# PotsDuino.net
KiCad netlist of a schematic drawn in Altium Designer
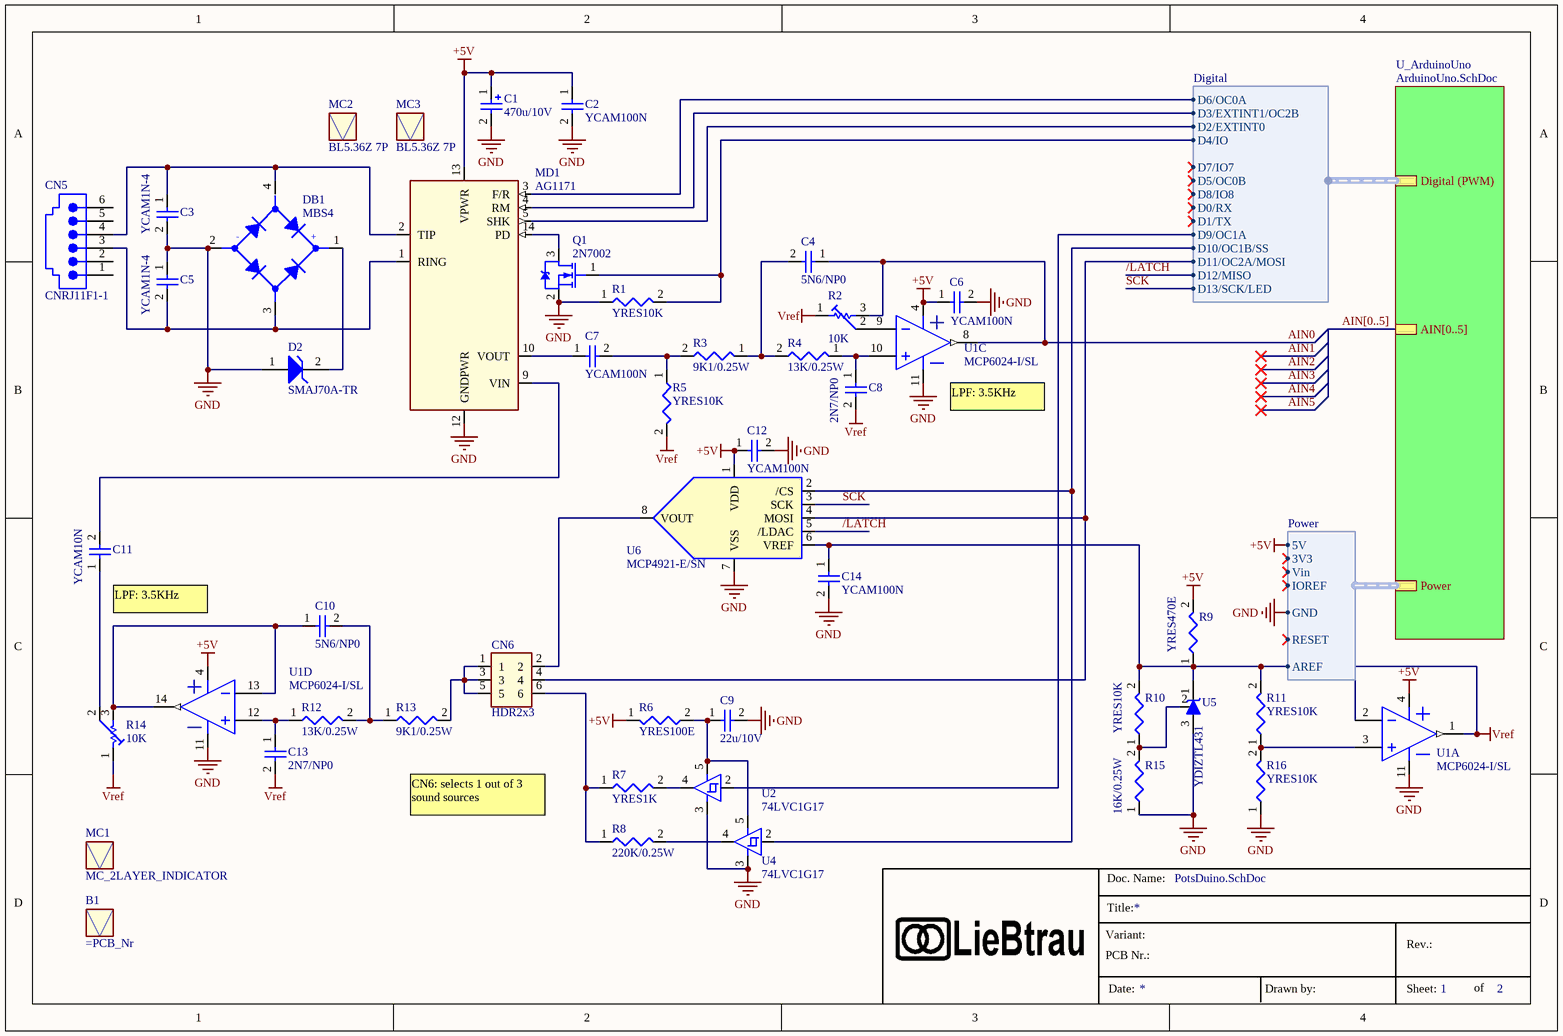
[diagram p0: PotsDuino.SchDoc]

(export (version "E")
  (design (tool "Eeschema 10.0.6"))
  (components
    (comp (ref "B1")
      (value "~")
      (fields (field (name "PART NUMBER") "BARE_PCB"))
      (libsource (lib "Testing") (part "BD_PCB"))
    )
    (comp (ref "C1")
      (value "470u/10V")
      (footprint "CA_CANSMD103_H100")
      (fields (field (name "PART NUMBER") "EEEFC1A471P") (field (name "MANUFACTURER") "Panasonic"))
      (libsource (lib "Testing") (part "CA_POL"))
    )
    (comp (ref "C2") (value "YCAM100N") (footprint "CA_1206") (libsource (lib "Testing") (part "CA_NONPOL")))
    (comp (ref "C3")
      (value "YCAM1N-4")
      (footprint "CA_1206_H16")
      (fields (field (name "MANUFACTURER") "AVX"))
      (libsource (lib "Testing") (part "CA_NONPOL"))
    )
    (comp (ref "C4")
      (value "5N6/NP0")
      (footprint "CA_0603")
      (fields (field (name "PART NUMBER") "C0603C562J5GACTU") (field (name "MANUFACTURER") "KEMET"))
      (libsource (lib "Testing") (part "CA_NONPOL"))
    )
    (comp (ref "C5")
      (value "YCAM1N-4")
      (footprint "CA_1206_H16")
      (fields (field (name "MANUFACTURER") "AVX"))
      (libsource (lib "Testing") (part "CA_NONPOL"))
    )
    (comp (ref "C6") (value "YCAM100N") (footprint "CA_1206") (libsource (lib "Testing") (part "CA_NONPOL")))
    (comp (ref "C7") (value "YCAM100N") (footprint "CA_1206") (libsource (lib "Testing") (part "CA_NONPOL")))
    (comp (ref "C8")
      (value "2N7/NP0")
      (footprint "CA_1206")
      (fields
        (field (name "PART NUMBER") "CC1206JRNPO9BN272")
        (field (name "MANUFACTURER") "YAGEO (PHYCOMP)")
      )
      (libsource (lib "Testing") (part "CA_NONPOL"))
    )
    (comp (ref "C9")
      (value "22u/10V")
      (footprint "CA_1206")
      (fields (field (name "PART NUMBER") "1206ZC226KAT2A") (field (name "MANUFACTURER") "AVX"))
      (libsource (lib "Testing") (part "CA_NONPOL"))
    )
    (comp (ref "C10")
      (value "5N6/NP0")
      (footprint "CA_0603")
      (fields (field (name "PART NUMBER") "C0603C562J5GACTU") (field (name "MANUFACTURER") "KEMET"))
      (libsource (lib "Testing") (part "CA_NONPOL"))
    )
    (comp (ref "C11")
      (value "YCAM10N")
      (footprint "CA_1206")
      (fields (field (name "MANUFACTURER") "Multicomp"))
      (libsource (lib "Testing") (part "CA_NONPOL"))
    )
    (comp (ref "C12") (value "YCAM100N") (footprint "CA_1206") (libsource (lib "Testing") (part "CA_NONPOL")))
    (comp (ref "C13")
      (value "2N7/NP0")
      (footprint "CA_1206")
      (fields
        (field (name "PART NUMBER") "CC1206JRNPO9BN272")
        (field (name "MANUFACTURER") "YAGEO (PHYCOMP)")
      )
      (libsource (lib "Testing") (part "CA_NONPOL"))
    )
    (comp (ref "C14") (value "YCAM100N") (footprint "CA_1206") (libsource (lib "Testing") (part "CA_NONPOL")))
    (comp (ref "CN5")
      (value "CNRJ11F1-1")
      (footprint "CN_MODJACK_6P")
      (libsource (lib "Testing") (part "CN_MODJACK_6P"))
    )
    (comp (ref "CN6")
      (value "HDR2x3")
      (footprint "CN_HDR2X3")
      (fields (field (name "PART NUMBER") "826656-3") (field (name "MANUFACTURER") "Tyco Electronics"))
      (libsource (lib "Testing") (part "CN_2x3P"))
    )
    (comp (ref "D2")
      (value "SMAJ70A-TR")
      (footprint "DI_DO-214AC")
      (fields (field (name "MANUFACTURER") "STMICROELECTRONICS"))
      (libsource (lib "Testing") (part "DI_ZENER"))
    )
    (comp (ref "DB1")
      (value "MBS4")
      (footprint "SC_SO4")
      (fields (field (name "MANUFACTURER") "TAIWAN SEMICONDUCTOR"))
      (libsource (lib "Testing") (part "DB_BRIDGE-RECT"))
    )
    (comp (ref "MC1")
      (value "MC_2LAYER_INDICATOR")
      (footprint "MC_2LAYER_INDICATOR")
      (libsource (lib "Testing") (part "MC_MechPart_No_BOM"))
    )
    (comp (ref "MC2")
      (value "BL5.36Z 7P")
      (footprint "CN_TOP_ENTRY_SOCKET_7P_NOHOLES")
      (fields
        (field (name "PART NUMBER") "BL5.36Z 7P MECH")
        (field (name "MANUFACTURER") "Fischer Elektronik")
      )
      (libsource (lib "Testing") (part "MC_MechPart"))
    )
    (comp (ref "MC3")
      (value "BL5.36Z 7P")
      (footprint "CN_TOP_ENTRY_SOCKET_7P_NOHOLES")
      (fields
        (field (name "PART NUMBER") "BL5.36Z 7P MECH")
        (field (name "MANUFACTURER") "Fischer Elektronik")
      )
      (libsource (lib "Testing") (part "MC_MechPart"))
    )
    (comp (ref "MD1")
      (value "AG1171")
      (footprint "MD_AG1171")
      (fields (field (name "MANUFACTURER") "Silvertel"))
      (libsource (lib "Testing") (part "MD_AG1171"))
    )
    (comp (ref "Q1") (value "2N7002") (footprint "SC_SOT23") (libsource (lib "Testing") (part "TR_NMOS")))
    (comp (ref "R1")
      (value "YRES10K")
      (footprint "RE_1206")
      (description "Resistor")
      (fields (field (name "MANUFACTURER") "Vishay Draloric"))
      (libsource (lib "Testing") (part "RE_RES"))
    )
    (comp (ref "R2")
      (value "10K")
      (footprint "RE_TRIM_BOURNS_67W")
      (fields
        (field (name "PART NUMBER") "67WR10KLF")
        (field (name "MANUFACTURER") "BI TECHNOLOGIES/TT ELECTRONICS")
      )
      (libsource (lib "Testing") (part "RE_TRIM"))
    )
    (comp (ref "R3")
      (value "9K1/0.25W")
      (footprint "RE_1206")
      (description "Resistor")
      (fields (field (name "PART NUMBER") "CRCW12069K10FKEA") (field (name "MANUFACTURER") "VISHAY DRALORIC"))
      (libsource (lib "Testing") (part "RE_RES"))
    )
    (comp (ref "R4")
      (value "13K/0.25W")
      (footprint "RE_1206")
      (description "Resistor")
      (fields (field (name "PART NUMBER") "MCMR12X1302FTL") (field (name "MANUFACTURER") "Multicomp"))
      (libsource (lib "Testing") (part "RE_RES"))
    )
    (comp (ref "R5")
      (value "YRES10K")
      (footprint "RE_1206")
      (description "Resistor")
      (fields (field (name "MANUFACTURER") "Vishay Draloric"))
      (libsource (lib "Testing") (part "RE_RES"))
    )
    (comp (ref "R6")
      (value "YRES100E")
      (footprint "RE_1206")
      (description "Resistor")
      (fields (field (name "MANUFACTURER") "Multicomp"))
      (libsource (lib "Testing") (part "RE_RES"))
    )
    (comp (ref "R7")
      (value "YRES1K")
      (footprint "RE_1206")
      (description "Resistor")
      (fields (field (name "MANUFACTURER") "Vishay Draloric"))
      (libsource (lib "Testing") (part "RE_RES"))
    )
    (comp (ref "R8")
      (value "220K/0.25W")
      (footprint "RE_1206")
      (description "Resistor")
      (fields (field (name "PART NUMBER") "RC1206FR-07220KL") (field (name "MANUFACTURER") "Yageo (Phycomp)"))
      (libsource (lib "Testing") (part "RE_RES"))
    )
    (comp (ref "R9")
      (value "YRES470E")
      (footprint "RE_1206")
      (description "Resistor")
      (fields (field (name "MANUFACTURER") "Multicomp"))
      (libsource (lib "Testing") (part "RE_RES"))
    )
    (comp (ref "R10")
      (value "YRES10K")
      (footprint "RE_1206")
      (description "Resistor")
      (fields (field (name "MANUFACTURER") "Vishay Draloric"))
      (libsource (lib "Testing") (part "RE_RES"))
    )
    (comp (ref "R11")
      (value "YRES10K")
      (footprint "RE_1206")
      (description "Resistor")
      (fields (field (name "MANUFACTURER") "Vishay Draloric"))
      (libsource (lib "Testing") (part "RE_RES"))
    )
    (comp (ref "R12")
      (value "13K/0.25W")
      (footprint "RE_1206")
      (description "Resistor")
      (fields (field (name "PART NUMBER") "MCMR12X1302FTL") (field (name "MANUFACTURER") "Multicomp"))
      (libsource (lib "Testing") (part "RE_RES"))
    )
    (comp (ref "R13")
      (value "9K1/0.25W")
      (footprint "RE_1206")
      (description "Resistor")
      (fields (field (name "PART NUMBER") "CRCW12069K10FKEA") (field (name "MANUFACTURER") "VISHAY DRALORIC"))
      (libsource (lib "Testing") (part "RE_RES"))
    )
    (comp (ref "R14")
      (value "10K")
      (footprint "RE_TRIM_BOURNS_67W")
      (fields
        (field (name "PART NUMBER") "67WR10KLF")
        (field (name "MANUFACTURER") "BI TECHNOLOGIES/TT ELECTRONICS")
      )
      (libsource (lib "Testing") (part "RE_TRIM"))
    )
    (comp (ref "R15")
      (value "16K/0.25W")
      (footprint "RE_1206")
      (description "Resistor")
      (fields (field (name "PART NUMBER") "CRCW120616K0FKEA") (field (name "MANUFACTURER") "Vishay Draloric"))
      (libsource (lib "Testing") (part "RE_RES"))
    )
    (comp (ref "R16")
      (value "YRES10K")
      (footprint "RE_1206")
      (description "Resistor")
      (fields (field (name "MANUFACTURER") "Vishay Draloric"))
      (libsource (lib "Testing") (part "RE_RES"))
    )
    (comp (ref "U1")
      (value "MCP6024-I/SL")
      (footprint "SC_SOIC14")
      (fields (field (name "MANUFACTURER") "Microchip"))
      (libsource (lib "Testing") (part "IC_OPAMP_QUAD"))
    )
    (comp (ref "U2")
      (value "74LVC1G17")
      (footprint "SC_SOT23-5AM")
      (fields (field (name "PART NUMBER") "74LVC1G17W5-7") (field (name "MANUFACTURER") "Diodes Inc."))
      (libsource (lib "Testing") (part "IC_74LVC1G17"))
    )
    (comp (ref "U4")
      (value "74LVC1G17")
      (footprint "SC_SOT23-5AM")
      (fields (field (name "PART NUMBER") "74LVC1G17W5-7") (field (name "MANUFACTURER") "Diodes Inc."))
      (libsource (lib "Testing") (part "IC_74LVC1G17"))
    )
    (comp (ref "U5")
      (value "YDIZTL431")
      (footprint "SC_SOT23")
      (fields (field (name "MANUFACTURER") "Diodes.Inc"))
      (libsource (lib "Testing") (part "IC_TL431"))
    )
    (comp (ref "U6")
      (value "MCP4921-E/SN")
      (footprint "SC_SOIC8")
      (fields (field (name "MANUFACTURER") "Microchip"))
      (libsource (lib "Testing") (part "IC_MCP4921"))
    )
  )
  (nets
    (net (code "3") (name "+5V") (class "Default")
      (node (ref "C1") (pin "1") (pinfunction "1_1") (pintype "passive"))
      (node (ref "C12") (pin "1") (pinfunction "1_1") (pintype "passive"))
      (node (ref "C2") (pin "1") (pinfunction "1_1") (pintype "passive"))
      (node (ref "C6") (pin "1") (pinfunction "1_1") (pintype "passive"))
      (node (ref "MD1") (pin "13") (pinfunction "VPWR_13") (pintype "passive"))
      (node (ref "R6") (pin "1") (pinfunction "1_1") (pintype "passive"))
      (node (ref "R9") (pin "2") (pinfunction "2_2") (pintype "passive"))
      (node (ref "U1") (pin "4") (pinfunction "VDD_4") (pintype "power_in"))
      (node (ref "U6") (pin "1") (pinfunction "VDD_1") (pintype "passive"))
    )
    (net (code "4") (name "/AIN0") (class "Default")
      (node (ref "C4") (pin "1") (pinfunction "1_1") (pintype "passive"))
      (node (ref "R2") (pin "3") (pinfunction "CW_3") (pintype "passive"))
      (node (ref "U1") (pin "8") (pinfunction "VOUTC_8") (pintype "output"))
    )
    (net (code "11") (name "/AREF") (class "Default")
      (node (ref "C14") (pin "1") (pinfunction "1_1") (pintype "passive"))
      (node (ref "R10") (pin "2") (pinfunction "2_2") (pintype "passive"))
      (node (ref "R11") (pin "2") (pinfunction "2_2") (pintype "passive"))
      (node (ref "R9") (pin "1") (pinfunction "1_1") (pintype "passive"))
      (node (ref "U5") (pin "1") (pinfunction "C_1") (pintype "passive"))
      (node (ref "U6") (pin "6") (pinfunction "VREF_6") (pintype "passive"))
    )
    (net (code "12") (name "/D2{slash}EXTINT0") (class "Default")
      (node (ref "MD1") (pin "5") (pinfunction "SHK_5") (pintype "output"))
    )
    (net (code "13") (name "/D3{slash}EXTINT1{slash}OC2B") (class "Default")
      (node (ref "MD1") (pin "4") (pinfunction "RM_4") (pintype "input"))
    )
    (net (code "14") (name "/D4{slash}IO") (class "Default")
      (node (ref "Q1") (pin "1") (pinfunction "G_1") (pintype "passive"))
      (node (ref "R1") (pin "2") (pinfunction "2_2") (pintype "passive"))
    )
    (net (code "15") (name "/D6{slash}OC0A") (class "Default")
      (node (ref "MD1") (pin "3") (pinfunction "F/R_3") (pintype "input"))
    )
    (net (code "16") (name "/D9{slash}OC1A") (class "Default")
      (node (ref "U2") (pin "2") (pinfunction "A_2") (pintype "passive"))
    )
    (net (code "17") (name "/D10{slash}OC1B{slash}SS") (class "Default")
      (node (ref "U4") (pin "2") (pinfunction "A_2") (pintype "passive"))
      (node (ref "U6") (pin "2") (pinfunction "/CS_2") (pintype "passive"))
    )
    (net (code "18") (name "/D11{slash}OC2A{slash}MOSI") (class "Default")
      (node (ref "CN6") (pin "4") (pinfunction "4_4") (pintype "passive"))
      (node (ref "U6") (pin "4") (pinfunction "MOSI_4") (pintype "passive"))
    )
    (net (code "19") (name "/SCK") (class "Default")
      (node (ref "U6") (pin "3") (pinfunction "SCK_3") (pintype "passive"))
    )
    (net (code "22") (name "/{slash}LATCH") (class "Default")
      (node (ref "U6") (pin "5") (pinfunction "/LDAC_5") (pintype "passive"))
    )
    (net (code "23") (name "GND") (class "Default")
      (node (ref "C1") (pin "2") (pinfunction "2_2") (pintype "passive"))
      (node (ref "C12") (pin "2") (pinfunction "2_2") (pintype "passive"))
      (node (ref "C14") (pin "2") (pinfunction "2_2") (pintype "passive"))
      (node (ref "C2") (pin "2") (pinfunction "2_2") (pintype "passive"))
      (node (ref "C3") (pin "2") (pinfunction "2_2") (pintype "passive"))
      (node (ref "C5") (pin "1") (pinfunction "1_1") (pintype "passive"))
      (node (ref "C6") (pin "2") (pinfunction "2_2") (pintype "passive"))
      (node (ref "C9") (pin "2") (pinfunction "2_2") (pintype "passive"))
      (node (ref "D2") (pin "1") (pinfunction "A_1") (pintype "passive"))
      (node (ref "DB1") (pin "2") (pinfunction "-DC_2") (pintype "passive"))
      (node (ref "MD1") (pin "12") (pinfunction "GNDPWR_12") (pintype "passive"))
      (node (ref "Q1") (pin "2") (pinfunction "S_2") (pintype "passive"))
      (node (ref "R1") (pin "1") (pinfunction "1_1") (pintype "passive"))
      (node (ref "R15") (pin "1") (pinfunction "1_1") (pintype "passive"))
      (node (ref "R16") (pin "1") (pinfunction "1_1") (pintype "passive"))
      (node (ref "U1") (pin "11") (pinfunction "VSS_11") (pintype "power_in"))
      (node (ref "U2") (pin "3") (pinfunction "A_3") (pintype "passive"))
      (node (ref "U4") (pin "3") (pinfunction "A_3") (pintype "passive"))
      (node (ref "U5") (pin "3") (pinfunction "A_3") (pintype "passive"))
      (node (ref "U6") (pin "7") (pinfunction "VSS_7") (pintype "passive"))
    )
    (net (code "24") (name "Net-(C4-Pad2)") (class "Default")
      (node (ref "C4") (pin "2") (pinfunction "2_2") (pintype "passive"))
      (node (ref "R3") (pin "1") (pinfunction "1_1") (pintype "passive"))
      (node (ref "R4") (pin "2") (pinfunction "2_2") (pintype "passive"))
    )
    (net (code "25") (name "Net-(C7-Pad2)") (class "Default")
      (node (ref "C7") (pin "2") (pinfunction "2_2") (pintype "passive"))
      (node (ref "R3") (pin "2") (pinfunction "2_2") (pintype "passive"))
      (node (ref "R5") (pin "1") (pinfunction "1_1") (pintype "passive"))
    )
    (net (code "26") (name "Net-(C9-Pad1)") (class "Default")
      (node (ref "C9") (pin "1") (pinfunction "1_1") (pintype "passive"))
      (node (ref "R6") (pin "2") (pinfunction "2_2") (pintype "passive"))
      (node (ref "U2") (pin "5") (pinfunction "A_5") (pintype "passive"))
      (node (ref "U4") (pin "5") (pinfunction "A_5") (pintype "passive"))
    )
    (net (code "27") (name "Net-(C10-Pad2)") (class "Default")
      (node (ref "C10") (pin "2") (pinfunction "2_2") (pintype "passive"))
      (node (ref "R12") (pin "2") (pinfunction "2_2") (pintype "passive"))
      (node (ref "R13") (pin "1") (pinfunction "1_1") (pintype "passive"))
    )
    (net (code "28") (name "Net-(CN6-Pad1)") (class "Default")
      (node (ref "CN6") (pin "1") (pinfunction "1_1") (pintype "passive"))
      (node (ref "CN6") (pin "3") (pinfunction "3_3") (pintype "passive"))
      (node (ref "CN6") (pin "5") (pinfunction "5_5") (pintype "passive"))
      (node (ref "R13") (pin "2") (pinfunction "2_2") (pintype "passive"))
    )
    (net (code "29") (name "Net-(CN6-Pad6)") (class "Default")
      (node (ref "CN6") (pin "6") (pinfunction "6_6") (pintype "passive"))
      (node (ref "R7") (pin "1") (pinfunction "1_1") (pintype "passive"))
      (node (ref "R8") (pin "1") (pinfunction "1_1") (pintype "passive"))
    )
    (net (code "30") (name "Net-(D2-K)") (class "Default")
      (node (ref "D2") (pin "2") (pinfunction "K_2") (pintype "passive"))
      (node (ref "DB1") (pin "1") (pinfunction "+DC_1") (pintype "passive"))
    )
    (net (code "31") (name "Net-(DB1-AC1)") (class "Default")
      (node (ref "C3") (pin "1") (pinfunction "1_1") (pintype "passive"))
      (node (ref "CN5") (pin "4") (pinfunction "4_4") (pintype "passive"))
      (node (ref "DB1") (pin "4") (pinfunction "AC1_4") (pintype "passive"))
      (node (ref "MD1") (pin "2") (pinfunction "TIP_2") (pintype "passive"))
    )
    (net (code "32") (name "Net-(DB1-AC2)") (class "Default")
      (node (ref "C5") (pin "2") (pinfunction "2_2") (pintype "passive"))
      (node (ref "CN5") (pin "3") (pinfunction "3_3") (pintype "passive"))
      (node (ref "DB1") (pin "3") (pinfunction "AC2_3") (pintype "passive"))
      (node (ref "MD1") (pin "1") (pinfunction "RING_1") (pintype "passive"))
    )
    (net (code "33") (name "Net-(MD1-PD)") (class "Default")
      (node (ref "MD1") (pin "14") (pinfunction "PD_14") (pintype "input"))
      (node (ref "Q1") (pin "3") (pinfunction "D_3") (pintype "passive"))
    )
    (net (code "34") (name "Net-(MD1-VIN)") (class "Default")
      (node (ref "C11") (pin "2") (pinfunction "2_2") (pintype "passive"))
      (node (ref "MD1") (pin "9") (pinfunction "VIN_9") (pintype "passive"))
    )
    (net (code "35") (name "Net-(MD1-VOUT)") (class "Default")
      (node (ref "C7") (pin "1") (pinfunction "1_1") (pintype "passive"))
      (node (ref "MD1") (pin "10") (pinfunction "VOUT_10") (pintype "passive"))
    )
    (net (code "36") (name "Net-(R2-TAP)") (class "Default")
      (node (ref "R2") (pin "2") (pinfunction "TAP_2") (pintype "passive"))
      (node (ref "U1") (pin "9") (pinfunction "VINC-_9") (pintype "passive"))
    )
    (net (code "37") (name "Net-(R7-Pad2)") (class "Default")
      (node (ref "R7") (pin "2") (pinfunction "2_2") (pintype "passive"))
      (node (ref "U2") (pin "4") (pinfunction "A_4") (pintype "passive"))
    )
    (net (code "38") (name "Net-(R8-Pad2)") (class "Default")
      (node (ref "R8") (pin "2") (pinfunction "2_2") (pintype "passive"))
      (node (ref "U4") (pin "4") (pinfunction "A_4") (pintype "passive"))
    )
    (net (code "39") (name "Net-(R14-CW)") (class "Default")
      (node (ref "C10") (pin "1") (pinfunction "1_1") (pintype "passive"))
      (node (ref "R14") (pin "3") (pinfunction "CW_3") (pintype "passive"))
      (node (ref "U1") (pin "13") (pinfunction "VIND-_13") (pintype "passive"))
      (node (ref "U1") (pin "14") (pinfunction "VOUTD_14") (pintype "output"))
    )
    (net (code "40") (name "Net-(R14-TAP)") (class "Default")
      (node (ref "C11") (pin "1") (pinfunction "1_1") (pintype "passive"))
      (node (ref "R14") (pin "2") (pinfunction "TAP_2") (pintype "passive"))
    )
    (net (code "41") (name "Net-(U1A-VINA+)") (class "Default")
      (node (ref "R11") (pin "1") (pinfunction "1_1") (pintype "passive"))
      (node (ref "R16") (pin "2") (pinfunction "2_2") (pintype "passive"))
      (node (ref "U1") (pin "3") (pinfunction "VINA+_3") (pintype "passive"))
    )
    (net (code "42") (name "Net-(U1C-VINC+)") (class "Default")
      (node (ref "C8") (pin "1") (pinfunction "1_1") (pintype "passive"))
      (node (ref "R4") (pin "1") (pinfunction "1_1") (pintype "passive"))
      (node (ref "U1") (pin "10") (pinfunction "VINC+_10") (pintype "passive"))
    )
    (net (code "43") (name "Net-(U1D-VIND+)") (class "Default")
      (node (ref "C13") (pin "1") (pinfunction "1_1") (pintype "passive"))
      (node (ref "R12") (pin "1") (pinfunction "1_1") (pintype "passive"))
      (node (ref "U1") (pin "12") (pinfunction "VIND+_12") (pintype "passive"))
    )
    (net (code "44") (name "Net-(U5-Ref)") (class "Default")
      (node (ref "R10") (pin "1") (pinfunction "1_1") (pintype "passive"))
      (node (ref "R15") (pin "2") (pinfunction "2_2") (pintype "passive"))
      (node (ref "U5") (pin "2") (pinfunction "Ref_2") (pintype "passive"))
    )
    (net (code "45") (name "Net-(U6-VOUT)") (class "Default")
      (node (ref "CN6") (pin "2") (pinfunction "2_2") (pintype "passive"))
      (node (ref "U6") (pin "8") (pinfunction "VOUT_8") (pintype "passive"))
    )
    (net (code "46") (name "Vref") (class "Default")
      (node (ref "C13") (pin "2") (pinfunction "2_2") (pintype "passive"))
      (node (ref "C8") (pin "2") (pinfunction "2_2") (pintype "passive"))
      (node (ref "R14") (pin "1") (pinfunction "CCW_1") (pintype "passive"))
      (node (ref "R2") (pin "1") (pinfunction "CCW_1") (pintype "passive"))
      (node (ref "R5") (pin "2") (pinfunction "2_2") (pintype "passive"))
      (node (ref "U1") (pin "1") (pinfunction "VOUTA_1") (pintype "output"))
      (node (ref "U1") (pin "2") (pinfunction "VINA-_2") (pintype "passive"))
    )
    (net (code "47") (name "unconnected-(CN5-Pad1)") (class "Default")
      (node (ref "CN5") (pin "1") (pinfunction "1_1") (pintype "passive"))
    )
    (net (code "48") (name "unconnected-(CN5-Pad2)") (class "Default")
      (node (ref "CN5") (pin "2") (pinfunction "2_2") (pintype "passive"))
    )
    (net (code "49") (name "unconnected-(CN5-Pad5)") (class "Default")
      (node (ref "CN5") (pin "5") (pinfunction "5_5") (pintype "passive"))
    )
    (net (code "50") (name "unconnected-(CN5-Pad6)") (class "Default")
      (node (ref "CN5") (pin "6") (pinfunction "6_6") (pintype "passive"))
    )
  )
)
